# picaxe28x1bb.net
KiCad netlist of a schematic drawn in EAGLE
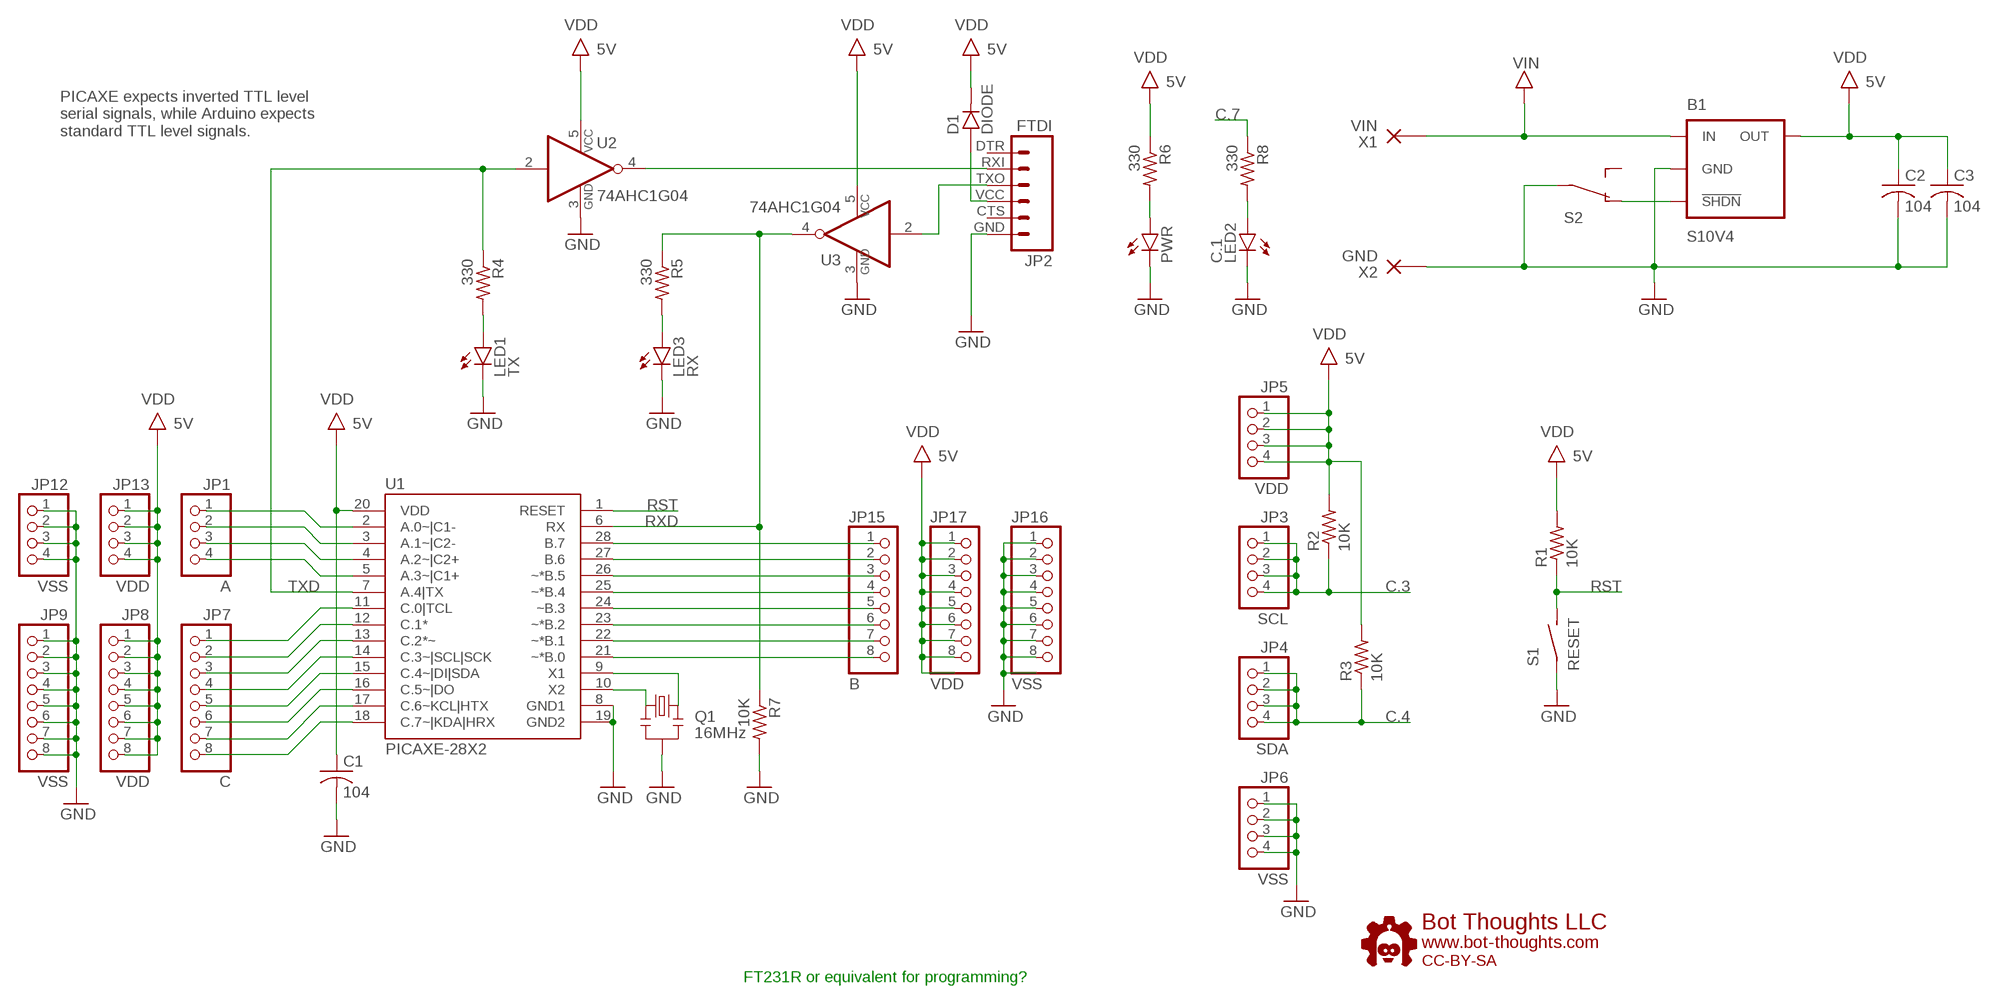
[diagram p0: schematic, sheet 1]

(export (version "E")
  (design (tool "Eeschema 10.0.6"))
  (components
    (comp (ref "B1")
      (value "S10V4")
      (footprint "eagle-import:POLOLU-S10V4")
      (libsource (lib "eagle-import") (part "POLOLU-S10V4"))
    )
    (comp (ref "C1")
      (value "104")
      (footprint "eagle-import:C0603")
      (libsource (lib "eagle-import") (part "C-USC0603"))
    )
    (comp (ref "C2")
      (value "104")
      (footprint "eagle-import:C0603")
      (libsource (lib "eagle-import") (part "C-USC0603"))
    )
    (comp (ref "C3")
      (value "104")
      (footprint "eagle-import:C0603")
      (libsource (lib "eagle-import") (part "C-USC0603"))
    )
    (comp (ref "D1")
      (value "DIODE")
      (footprint "eagle-import:SOD123FL")
      (libsource (lib "eagle-import") (part "DIODE_SOD123FL"))
    )
    (comp (ref "JP1")
      (value "A")
      (footprint "eagle-import:1X04-S")
      (libsource (lib "eagle-import") (part "PINHD-1X04_2.54-S"))
    )
    (comp (ref "JP2")
      (value "FTDI")
      (footprint "eagle-import:FTDI_BASIC")
      (libsource (lib "eagle-import") (part "FTDI_BASICPTH"))
    )
    (comp (ref "JP3")
      (value "SCL")
      (footprint "eagle-import:1X04-S")
      (libsource (lib "eagle-import") (part "PINHD-1X04_2.54-S"))
    )
    (comp (ref "JP4")
      (value "SDA")
      (footprint "eagle-import:1X04-S")
      (libsource (lib "eagle-import") (part "PINHD-1X04_2.54-S"))
    )
    (comp (ref "JP5")
      (value "VDD")
      (footprint "eagle-import:1X04-S")
      (libsource (lib "eagle-import") (part "PINHD-1X04_2.54-S"))
    )
    (comp (ref "JP6")
      (value "VSS")
      (footprint "eagle-import:1X04-S")
      (libsource (lib "eagle-import") (part "PINHD-1X04_2.54-S"))
    )
    (comp (ref "JP7")
      (value "C")
      (footprint "eagle-import:1X08-S")
      (libsource (lib "eagle-import") (part "PINHD-1X08_2.54-S"))
    )
    (comp (ref "JP8")
      (value "VDD")
      (footprint "eagle-import:1X08-S")
      (libsource (lib "eagle-import") (part "PINHD-1X08_2.54-S"))
    )
    (comp (ref "JP9")
      (value "VSS")
      (footprint "eagle-import:1X08-S")
      (libsource (lib "eagle-import") (part "PINHD-1X08_2.54-S"))
    )
    (comp (ref "JP12")
      (value "VSS")
      (footprint "eagle-import:1X04-S")
      (libsource (lib "eagle-import") (part "PINHD-1X04_2.54-S"))
    )
    (comp (ref "JP13")
      (value "VDD")
      (footprint "eagle-import:1X04-S")
      (libsource (lib "eagle-import") (part "PINHD-1X04_2.54-S"))
    )
    (comp (ref "JP15")
      (value "B")
      (footprint "eagle-import:1X08-S")
      (libsource (lib "eagle-import") (part "PINHD-1X08_2.54-S"))
    )
    (comp (ref "JP16")
      (value "VSS")
      (footprint "eagle-import:1X08-S")
      (libsource (lib "eagle-import") (part "PINHD-1X08_2.54-S"))
    )
    (comp (ref "JP17")
      (value "VDD")
      (footprint "eagle-import:1X08-S")
      (libsource (lib "eagle-import") (part "PINHD-1X08_2.54-S"))
    )
    (comp (ref "LED1")
      (value "TX")
      (footprint "eagle-import:CHIPLED_0805")
      (libsource (lib "eagle-import") (part "LEDCHIPLED_0805"))
    )
    (comp (ref "LED2")
      (value "C.1")
      (footprint "eagle-import:CHIPLED_0805")
      (libsource (lib "eagle-import") (part "LEDCHIPLED_0805"))
    )
    (comp (ref "LED3")
      (value "RX")
      (footprint "eagle-import:CHIPLED_0805")
      (libsource (lib "eagle-import") (part "LEDCHIPLED_0805"))
    )
    (comp (ref "PWR")
      (value "LEDCHIPLED_0805")
      (footprint "eagle-import:CHIPLED_0805")
      (libsource (lib "eagle-import") (part "LEDCHIPLED_0805"))
    )
    (comp (ref "Q1")
      (value "16MHz")
      (footprint "eagle-import:CSTCE_V_C")
      (libsource (lib "eagle-import") (part "RESONATOR_CSTCE_V_C"))
    )
    (comp (ref "R1")
      (value "10K")
      (footprint "eagle-import:R0603")
      (libsource (lib "eagle-import") (part "R-US_R0603"))
    )
    (comp (ref "R2")
      (value "10K")
      (footprint "eagle-import:R0603")
      (libsource (lib "eagle-import") (part "R-US_R0603"))
    )
    (comp (ref "R3")
      (value "10K")
      (footprint "eagle-import:R0603")
      (libsource (lib "eagle-import") (part "R-US_R0603"))
    )
    (comp (ref "R4")
      (value "330")
      (footprint "eagle-import:R0603")
      (libsource (lib "eagle-import") (part "R-US_R0603"))
    )
    (comp (ref "R5")
      (value "330")
      (footprint "eagle-import:R0603")
      (libsource (lib "eagle-import") (part "R-US_R0603"))
    )
    (comp (ref "R6")
      (value "330")
      (footprint "eagle-import:R0603")
      (libsource (lib "eagle-import") (part "R-US_R0603"))
    )
    (comp (ref "R7")
      (value "10K")
      (footprint "eagle-import:R0603")
      (libsource (lib "eagle-import") (part "R-US_R0603"))
    )
    (comp (ref "R8")
      (value "330")
      (footprint "eagle-import:R0603")
      (libsource (lib "eagle-import") (part "R-US_R0603"))
    )
    (comp (ref "S1")
      (value "RESET")
      (footprint "eagle-import:3X4X2TACT")
      (libsource (lib "eagle-import") (part "SPST_3X4X2"))
    )
    (comp (ref "S2")
      (value "SPDT_OS102011MAQN1")
      (footprint "eagle-import:OS102011MA1Q")
      (libsource (lib "eagle-import") (part "SPDT_OS102011MAQN1"))
    )
    (comp (ref "U$10")
      (value "BTLOGO-LOGO-MD")
      (footprint "eagle-import:BTLOGOM")
      (libsource (lib "eagle-import") (part "BTLOGO-LOGO-MD"))
    )
    (comp (ref "U1")
      (value "PICAXE-28X2")
      (footprint "eagle-import:DIL28-3")
      (libsource (lib "eagle-import") (part "PICAXE-28X2"))
    )
    (comp (ref "U2")
      (value "74AHC1G04")
      (footprint "eagle-import:SOT23-5")
      (libsource (lib "eagle-import") (part "741G04DBVAHC"))
    )
    (comp (ref "U3")
      (value "74AHC1G04")
      (footprint "eagle-import:SOT23-5")
      (libsource (lib "eagle-import") (part "741G04DBVAHC"))
    )
    (comp (ref "X1")
      (value "VIN")
      (footprint "eagle-import:PAD_18GA")
      (libsource (lib "eagle-import") (part "WIREPAD_18GA"))
    )
    (comp (ref "X2")
      (value "GND")
      (footprint "eagle-import:PAD_18GA")
      (libsource (lib "eagle-import") (part "WIREPAD_18GA"))
    )
  )
  (nets
    (net (code "1") (name "/C.3") (class "Default")
      (node (ref "JP3") (pin "1") (pinfunction "1_1") (pintype "passive"))
      (node (ref "JP3") (pin "2") (pinfunction "2_2") (pintype "passive"))
      (node (ref "JP3") (pin "3") (pinfunction "3_3") (pintype "passive"))
      (node (ref "JP3") (pin "4") (pinfunction "4_4") (pintype "passive"))
      (node (ref "JP7") (pin "4") (pinfunction "4_4") (pintype "passive"))
      (node (ref "R2") (pin "1") (pinfunction "1_1") (pintype "passive"))
      (node (ref "U1") (pin "14") (pinfunction "C.3~{|SCL|SCK}_14") (pintype "bidirectional"))
    )
    (net (code "2") (name "/C.4") (class "Default")
      (node (ref "JP4") (pin "1") (pinfunction "1_1") (pintype "passive"))
      (node (ref "JP4") (pin "2") (pinfunction "2_2") (pintype "passive"))
      (node (ref "JP4") (pin "3") (pinfunction "3_3") (pintype "passive"))
      (node (ref "JP4") (pin "4") (pinfunction "4_4") (pintype "passive"))
      (node (ref "JP7") (pin "5") (pinfunction "5_5") (pintype "passive"))
      (node (ref "R3") (pin "1") (pinfunction "1_1") (pintype "passive"))
      (node (ref "U1") (pin "15") (pinfunction "C.4~{|DI|SDA}_15") (pintype "bidirectional"))
    )
    (net (code "3") (name "/C.7") (class "Default")
      (node (ref "JP7") (pin "8") (pinfunction "8_8") (pintype "passive"))
      (node (ref "R8") (pin "1") (pinfunction "1_1") (pintype "passive"))
      (node (ref "U1") (pin "18") (pinfunction "C.7~{|KDA|HRX}_18") (pintype "bidirectional"))
    )
    (net (code "4") (name "/RST") (class "Default")
      (node (ref "R1") (pin "1") (pinfunction "1_1") (pintype "passive"))
      (node (ref "S1") (pin "P$2") (pinfunction "S_P$2") (pintype "passive"))
      (node (ref "U1") (pin "1") (pinfunction "RESET_1") (pintype "bidirectional"))
    )
    (net (code "5") (name "/RXD") (class "Default")
      (node (ref "R5") (pin "1") (pinfunction "1_1") (pintype "passive"))
      (node (ref "R7") (pin "1") (pinfunction "1_1") (pintype "passive"))
      (node (ref "U1") (pin "6") (pinfunction "RX_6") (pintype "input"))
      (node (ref "U3") (pin "4") (pinfunction "O_4") (pintype "output"))
    )
    (net (code "6") (name "/TXD") (class "Default")
      (node (ref "R4") (pin "1") (pinfunction "1_1") (pintype "passive"))
      (node (ref "U1") (pin "7") (pinfunction "A.4|TX_7") (pintype "output"))
      (node (ref "U2") (pin "2") (pinfunction "I_2") (pintype "input"))
    )
    (net (code "7") (name "5V") (class "Default")
      (node (ref "B1") (pin "VOUT") (pinfunction "OUT_VOUT") (pintype "passive"))
      (node (ref "C1") (pin "1") (pinfunction "1_1") (pintype "passive"))
      (node (ref "C2") (pin "1") (pinfunction "1_1") (pintype "passive"))
      (node (ref "C3") (pin "1") (pinfunction "1_1") (pintype "passive"))
      (node (ref "D1") (pin "C") (pinfunction "C_C") (pintype "passive"))
      (node (ref "JP13") (pin "1") (pinfunction "1_1") (pintype "passive"))
      (node (ref "JP13") (pin "2") (pinfunction "2_2") (pintype "passive"))
      (node (ref "JP13") (pin "3") (pinfunction "3_3") (pintype "passive"))
      (node (ref "JP13") (pin "4") (pinfunction "4_4") (pintype "passive"))
      (node (ref "JP17") (pin "1") (pinfunction "1_1") (pintype "passive"))
      (node (ref "JP17") (pin "2") (pinfunction "2_2") (pintype "passive"))
      (node (ref "JP17") (pin "3") (pinfunction "3_3") (pintype "passive"))
      (node (ref "JP17") (pin "4") (pinfunction "4_4") (pintype "passive"))
      (node (ref "JP17") (pin "5") (pinfunction "5_5") (pintype "passive"))
      (node (ref "JP17") (pin "6") (pinfunction "6_6") (pintype "passive"))
      (node (ref "JP17") (pin "7") (pinfunction "7_7") (pintype "passive"))
      (node (ref "JP17") (pin "8") (pinfunction "8_8") (pintype "passive"))
      (node (ref "JP5") (pin "1") (pinfunction "1_1") (pintype "passive"))
      (node (ref "JP5") (pin "2") (pinfunction "2_2") (pintype "passive"))
      (node (ref "JP5") (pin "3") (pinfunction "3_3") (pintype "passive"))
      (node (ref "JP5") (pin "4") (pinfunction "4_4") (pintype "passive"))
      (node (ref "JP8") (pin "1") (pinfunction "1_1") (pintype "passive"))
      (node (ref "JP8") (pin "2") (pinfunction "2_2") (pintype "passive"))
      (node (ref "JP8") (pin "3") (pinfunction "3_3") (pintype "passive"))
      (node (ref "JP8") (pin "4") (pinfunction "4_4") (pintype "passive"))
      (node (ref "JP8") (pin "5") (pinfunction "5_5") (pintype "passive"))
      (node (ref "JP8") (pin "6") (pinfunction "6_6") (pintype "passive"))
      (node (ref "JP8") (pin "7") (pinfunction "7_7") (pintype "passive"))
      (node (ref "JP8") (pin "8") (pinfunction "8_8") (pintype "passive"))
      (node (ref "R1") (pin "2") (pinfunction "2_2") (pintype "passive"))
      (node (ref "R2") (pin "2") (pinfunction "2_2") (pintype "passive"))
      (node (ref "R3") (pin "2") (pinfunction "2_2") (pintype "passive"))
      (node (ref "R6") (pin "1") (pinfunction "1_1") (pintype "passive"))
      (node (ref "U1") (pin "20") (pinfunction "VDD_20") (pintype "power_in"))
      (node (ref "U2") (pin "5") (pinfunction "VCC_5") (pintype "power_in"))
      (node (ref "U3") (pin "5") (pinfunction "VCC_5") (pintype "power_in"))
    )
    (net (code "8") (name "GND") (class "Default")
      (node (ref "B1") (pin "GND") (pinfunction "GND_GND") (pintype "input"))
      (node (ref "C1") (pin "2") (pinfunction "2_2") (pintype "passive"))
      (node (ref "C2") (pin "2") (pinfunction "2_2") (pintype "passive"))
      (node (ref "C3") (pin "2") (pinfunction "2_2") (pintype "passive"))
      (node (ref "JP12") (pin "1") (pinfunction "1_1") (pintype "passive"))
      (node (ref "JP12") (pin "2") (pinfunction "2_2") (pintype "passive"))
      (node (ref "JP12") (pin "3") (pinfunction "3_3") (pintype "passive"))
      (node (ref "JP12") (pin "4") (pinfunction "4_4") (pintype "passive"))
      (node (ref "JP16") (pin "1") (pinfunction "1_1") (pintype "passive"))
      (node (ref "JP16") (pin "2") (pinfunction "2_2") (pintype "passive"))
      (node (ref "JP16") (pin "3") (pinfunction "3_3") (pintype "passive"))
      (node (ref "JP16") (pin "4") (pinfunction "4_4") (pintype "passive"))
      (node (ref "JP16") (pin "5") (pinfunction "5_5") (pintype "passive"))
      (node (ref "JP16") (pin "6") (pinfunction "6_6") (pintype "passive"))
      (node (ref "JP16") (pin "7") (pinfunction "7_7") (pintype "passive"))
      (node (ref "JP16") (pin "8") (pinfunction "8_8") (pintype "passive"))
      (node (ref "JP2") (pin "GND") (pinfunction "6_GND") (pintype "passive"))
      (node (ref "JP6") (pin "1") (pinfunction "1_1") (pintype "passive"))
      (node (ref "JP6") (pin "2") (pinfunction "2_2") (pintype "passive"))
      (node (ref "JP6") (pin "3") (pinfunction "3_3") (pintype "passive"))
      (node (ref "JP6") (pin "4") (pinfunction "4_4") (pintype "passive"))
      (node (ref "JP9") (pin "1") (pinfunction "1_1") (pintype "passive"))
      (node (ref "JP9") (pin "2") (pinfunction "2_2") (pintype "passive"))
      (node (ref "JP9") (pin "3") (pinfunction "3_3") (pintype "passive"))
      (node (ref "JP9") (pin "4") (pinfunction "4_4") (pintype "passive"))
      (node (ref "JP9") (pin "5") (pinfunction "5_5") (pintype "passive"))
      (node (ref "JP9") (pin "6") (pinfunction "6_6") (pintype "passive"))
      (node (ref "JP9") (pin "7") (pinfunction "7_7") (pintype "passive"))
      (node (ref "JP9") (pin "8") (pinfunction "8_8") (pintype "passive"))
      (node (ref "LED1") (pin "C") (pinfunction "C_C") (pintype "passive"))
      (node (ref "LED2") (pin "C") (pinfunction "C_C") (pintype "passive"))
      (node (ref "LED3") (pin "C") (pinfunction "C_C") (pintype "passive"))
      (node (ref "PWR") (pin "C") (pinfunction "C_C") (pintype "passive"))
      (node (ref "Q1") (pin "GND") (pinfunction "GND_GND") (pintype "passive"))
      (node (ref "R7") (pin "2") (pinfunction "2_2") (pintype "passive"))
      (node (ref "S1") (pin "P$1") (pinfunction "P_P$1") (pintype "passive"))
      (node (ref "S2") (pin "P$2") (pinfunction "P_P$2") (pintype "passive"))
      (node (ref "U1") (pin "19") (pinfunction "GND2_19") (pintype "power_in"))
      (node (ref "U1") (pin "8") (pinfunction "GND1_8") (pintype "power_in"))
      (node (ref "U2") (pin "3") (pinfunction "GND_3") (pintype "power_in"))
      (node (ref "U3") (pin "3") (pinfunction "GND_3") (pintype "power_in"))
      (node (ref "X2") (pin "P$1") (pinfunction "P_P$1") (pintype "bidirectional"))
    )
    (net (code "9") (name "Net-(B1-~{SHDN})") (class "Default")
      (node (ref "B1") (pin "!SHDN") (pinfunction "~{SHDN}_!SHDN") (pintype "input"))
      (node (ref "S2") (pin "P$1") (pinfunction "O1_P$1") (pintype "passive"))
    )
    (net (code "10") (name "Net-(JP2-2)") (class "Default")
      (node (ref "JP2") (pin "RXI") (pinfunction "2_RXI") (pintype "passive"))
      (node (ref "U2") (pin "4") (pinfunction "O_4") (pintype "output"))
    )
    (net (code "11") (name "Net-(JP2-3)") (class "Default")
      (node (ref "JP2") (pin "TXO") (pinfunction "3_TXO") (pintype "passive"))
      (node (ref "U3") (pin "2") (pinfunction "I_2") (pintype "input"))
    )
    (net (code "12") (name "Net-(JP2-4)") (class "Default")
      (node (ref "D1") (pin "A") (pinfunction "A_A") (pintype "passive"))
      (node (ref "JP2") (pin "VCC") (pinfunction "4_VCC") (pintype "passive"))
    )
    (net (code "13") (name "Net-(LED1-PadA)") (class "Default")
      (node (ref "LED1") (pin "A") (pinfunction "A_A") (pintype "passive"))
      (node (ref "R4") (pin "2") (pinfunction "2_2") (pintype "passive"))
    )
    (net (code "14") (name "Net-(LED2-PadA)") (class "Default")
      (node (ref "LED2") (pin "A") (pinfunction "A_A") (pintype "passive"))
      (node (ref "R8") (pin "2") (pinfunction "2_2") (pintype "passive"))
    )
    (net (code "15") (name "Net-(LED3-PadA)") (class "Default")
      (node (ref "LED3") (pin "A") (pinfunction "A_A") (pintype "passive"))
      (node (ref "R5") (pin "2") (pinfunction "2_2") (pintype "passive"))
    )
    (net (code "16") (name "Net-(PWR-PadA)") (class "Default")
      (node (ref "PWR") (pin "A") (pinfunction "A_A") (pintype "passive"))
      (node (ref "R6") (pin "2") (pinfunction "2_2") (pintype "passive"))
    )
    (net (code "17") (name "Net-(U1-A.0~{|C1-})") (class "Default")
      (node (ref "JP1") (pin "1") (pinfunction "1_1") (pintype "passive"))
      (node (ref "U1") (pin "2") (pinfunction "A.0~{|C1-}_2") (pintype "bidirectional"))
    )
    (net (code "18") (name "Net-(U1-A.1~{|C2-})") (class "Default")
      (node (ref "JP1") (pin "2") (pinfunction "2_2") (pintype "passive"))
      (node (ref "U1") (pin "3") (pinfunction "A.1~{|C2-}_3") (pintype "bidirectional"))
    )
    (net (code "19") (name "Net-(U1-A.2~{|C2+})") (class "Default")
      (node (ref "JP1") (pin "3") (pinfunction "3_3") (pintype "passive"))
      (node (ref "U1") (pin "4") (pinfunction "A.2~{|C2+}_4") (pintype "bidirectional"))
    )
    (net (code "20") (name "Net-(U1-A.3~{|C1+})") (class "Default")
      (node (ref "JP1") (pin "4") (pinfunction "4_4") (pintype "passive"))
      (node (ref "U1") (pin "5") (pinfunction "A.3~{|C1+}_5") (pintype "bidirectional"))
    )
    (net (code "21") (name "Net-(U1-B.6)") (class "Default")
      (node (ref "JP15") (pin "2") (pinfunction "2_2") (pintype "passive"))
      (node (ref "U1") (pin "27") (pinfunction "B.6_27") (pintype "bidirectional"))
    )
    (net (code "22") (name "Net-(U1-B.7)") (class "Default")
      (node (ref "JP15") (pin "1") (pinfunction "1_1") (pintype "passive"))
      (node (ref "U1") (pin "28") (pinfunction "B.7_28") (pintype "bidirectional"))
    )
    (net (code "23") (name "Net-(U1-C.0|TCL)") (class "Default")
      (node (ref "JP7") (pin "1") (pinfunction "1_1") (pintype "passive"))
      (node (ref "U1") (pin "11") (pinfunction "C.0|TCL_11") (pintype "bidirectional"))
    )
    (net (code "24") (name "Net-(U1-C.1*)") (class "Default")
      (node (ref "JP7") (pin "2") (pinfunction "2_2") (pintype "passive"))
      (node (ref "U1") (pin "12") (pinfunction "C.1*_12") (pintype "bidirectional"))
    )
    (net (code "25") (name "Net-(U1-C.2*~{})") (class "Default")
      (node (ref "JP7") (pin "3") (pinfunction "3_3") (pintype "passive"))
      (node (ref "U1") (pin "13") (pinfunction "C.2*~{}_13") (pintype "bidirectional"))
    )
    (net (code "26") (name "Net-(U1-C.5~{|DO})") (class "Default")
      (node (ref "JP7") (pin "6") (pinfunction "6_6") (pintype "passive"))
      (node (ref "U1") (pin "16") (pinfunction "C.5~{|DO}_16") (pintype "bidirectional"))
    )
    (net (code "27") (name "Net-(U1-C.6~{KCL|HTX})") (class "Default")
      (node (ref "JP7") (pin "7") (pinfunction "7_7") (pintype "passive"))
      (node (ref "U1") (pin "17") (pinfunction "C.6~{KCL|HTX}_17") (pintype "bidirectional"))
    )
    (net (code "28") (name "Net-(U1-X1)") (class "Default")
      (node (ref "Q1") (pin "X1") (pinfunction "X1_X1") (pintype "passive"))
      (node (ref "U1") (pin "9") (pinfunction "X1_9") (pintype "bidirectional"))
    )
    (net (code "29") (name "Net-(U1-X2)") (class "Default")
      (node (ref "Q1") (pin "X2") (pinfunction "X2_X2") (pintype "passive"))
      (node (ref "U1") (pin "10") (pinfunction "X2_10") (pintype "bidirectional"))
    )
    (net (code "30") (name "Net-(U1-~{*B.0})") (class "Default")
      (node (ref "JP15") (pin "8") (pinfunction "8_8") (pintype "passive"))
      (node (ref "U1") (pin "21") (pinfunction "~{*B.0}_21") (pintype "bidirectional"))
    )
    (net (code "31") (name "Net-(U1-~{*B.1})") (class "Default")
      (node (ref "JP15") (pin "7") (pinfunction "7_7") (pintype "passive"))
      (node (ref "U1") (pin "22") (pinfunction "~{*B.1}_22") (pintype "bidirectional"))
    )
    (net (code "32") (name "Net-(U1-~{*B.2})") (class "Default")
      (node (ref "JP15") (pin "6") (pinfunction "6_6") (pintype "passive"))
      (node (ref "U1") (pin "23") (pinfunction "~{*B.2}_23") (pintype "bidirectional"))
    )
    (net (code "33") (name "Net-(U1-~{*B.4})") (class "Default")
      (node (ref "JP15") (pin "4") (pinfunction "4_4") (pintype "passive"))
      (node (ref "U1") (pin "25") (pinfunction "~{*B.4}_25") (pintype "bidirectional"))
    )
    (net (code "34") (name "Net-(U1-~{*B.5})") (class "Default")
      (node (ref "JP15") (pin "3") (pinfunction "3_3") (pintype "passive"))
      (node (ref "U1") (pin "26") (pinfunction "~{*B.5}_26") (pintype "bidirectional"))
    )
    (net (code "35") (name "Net-(U1-~{B.3})") (class "Default")
      (node (ref "JP15") (pin "5") (pinfunction "5_5") (pintype "passive"))
      (node (ref "U1") (pin "24") (pinfunction "~{B.3}_24") (pintype "bidirectional"))
    )
    (net (code "36") (name "VIN") (class "Default")
      (node (ref "B1") (pin "VIN") (pinfunction "IN_VIN") (pintype "input"))
      (node (ref "X1") (pin "P$1") (pinfunction "P_P$1") (pintype "bidirectional"))
    )
    (net (code "37") (name "unconnected-(JP2-1-PadDTR)") (class "Default")
      (node (ref "JP2") (pin "DTR") (pinfunction "1_DTR") (pintype "passive"))
    )
    (net (code "38") (name "unconnected-(JP2-5-PadCTS)") (class "Default")
      (node (ref "JP2") (pin "CTS") (pinfunction "5_CTS") (pintype "passive"))
    )
    (net (code "39") (name "unconnected-(S2-O2-PadP$3)") (class "Default")
      (node (ref "S2") (pin "P$3") (pinfunction "O2_P$3") (pintype "passive"))
    )
  )
)
